# chip-z8530-rs422_split_a.net
KiCad netlist of a schematic drawn in EAGLE
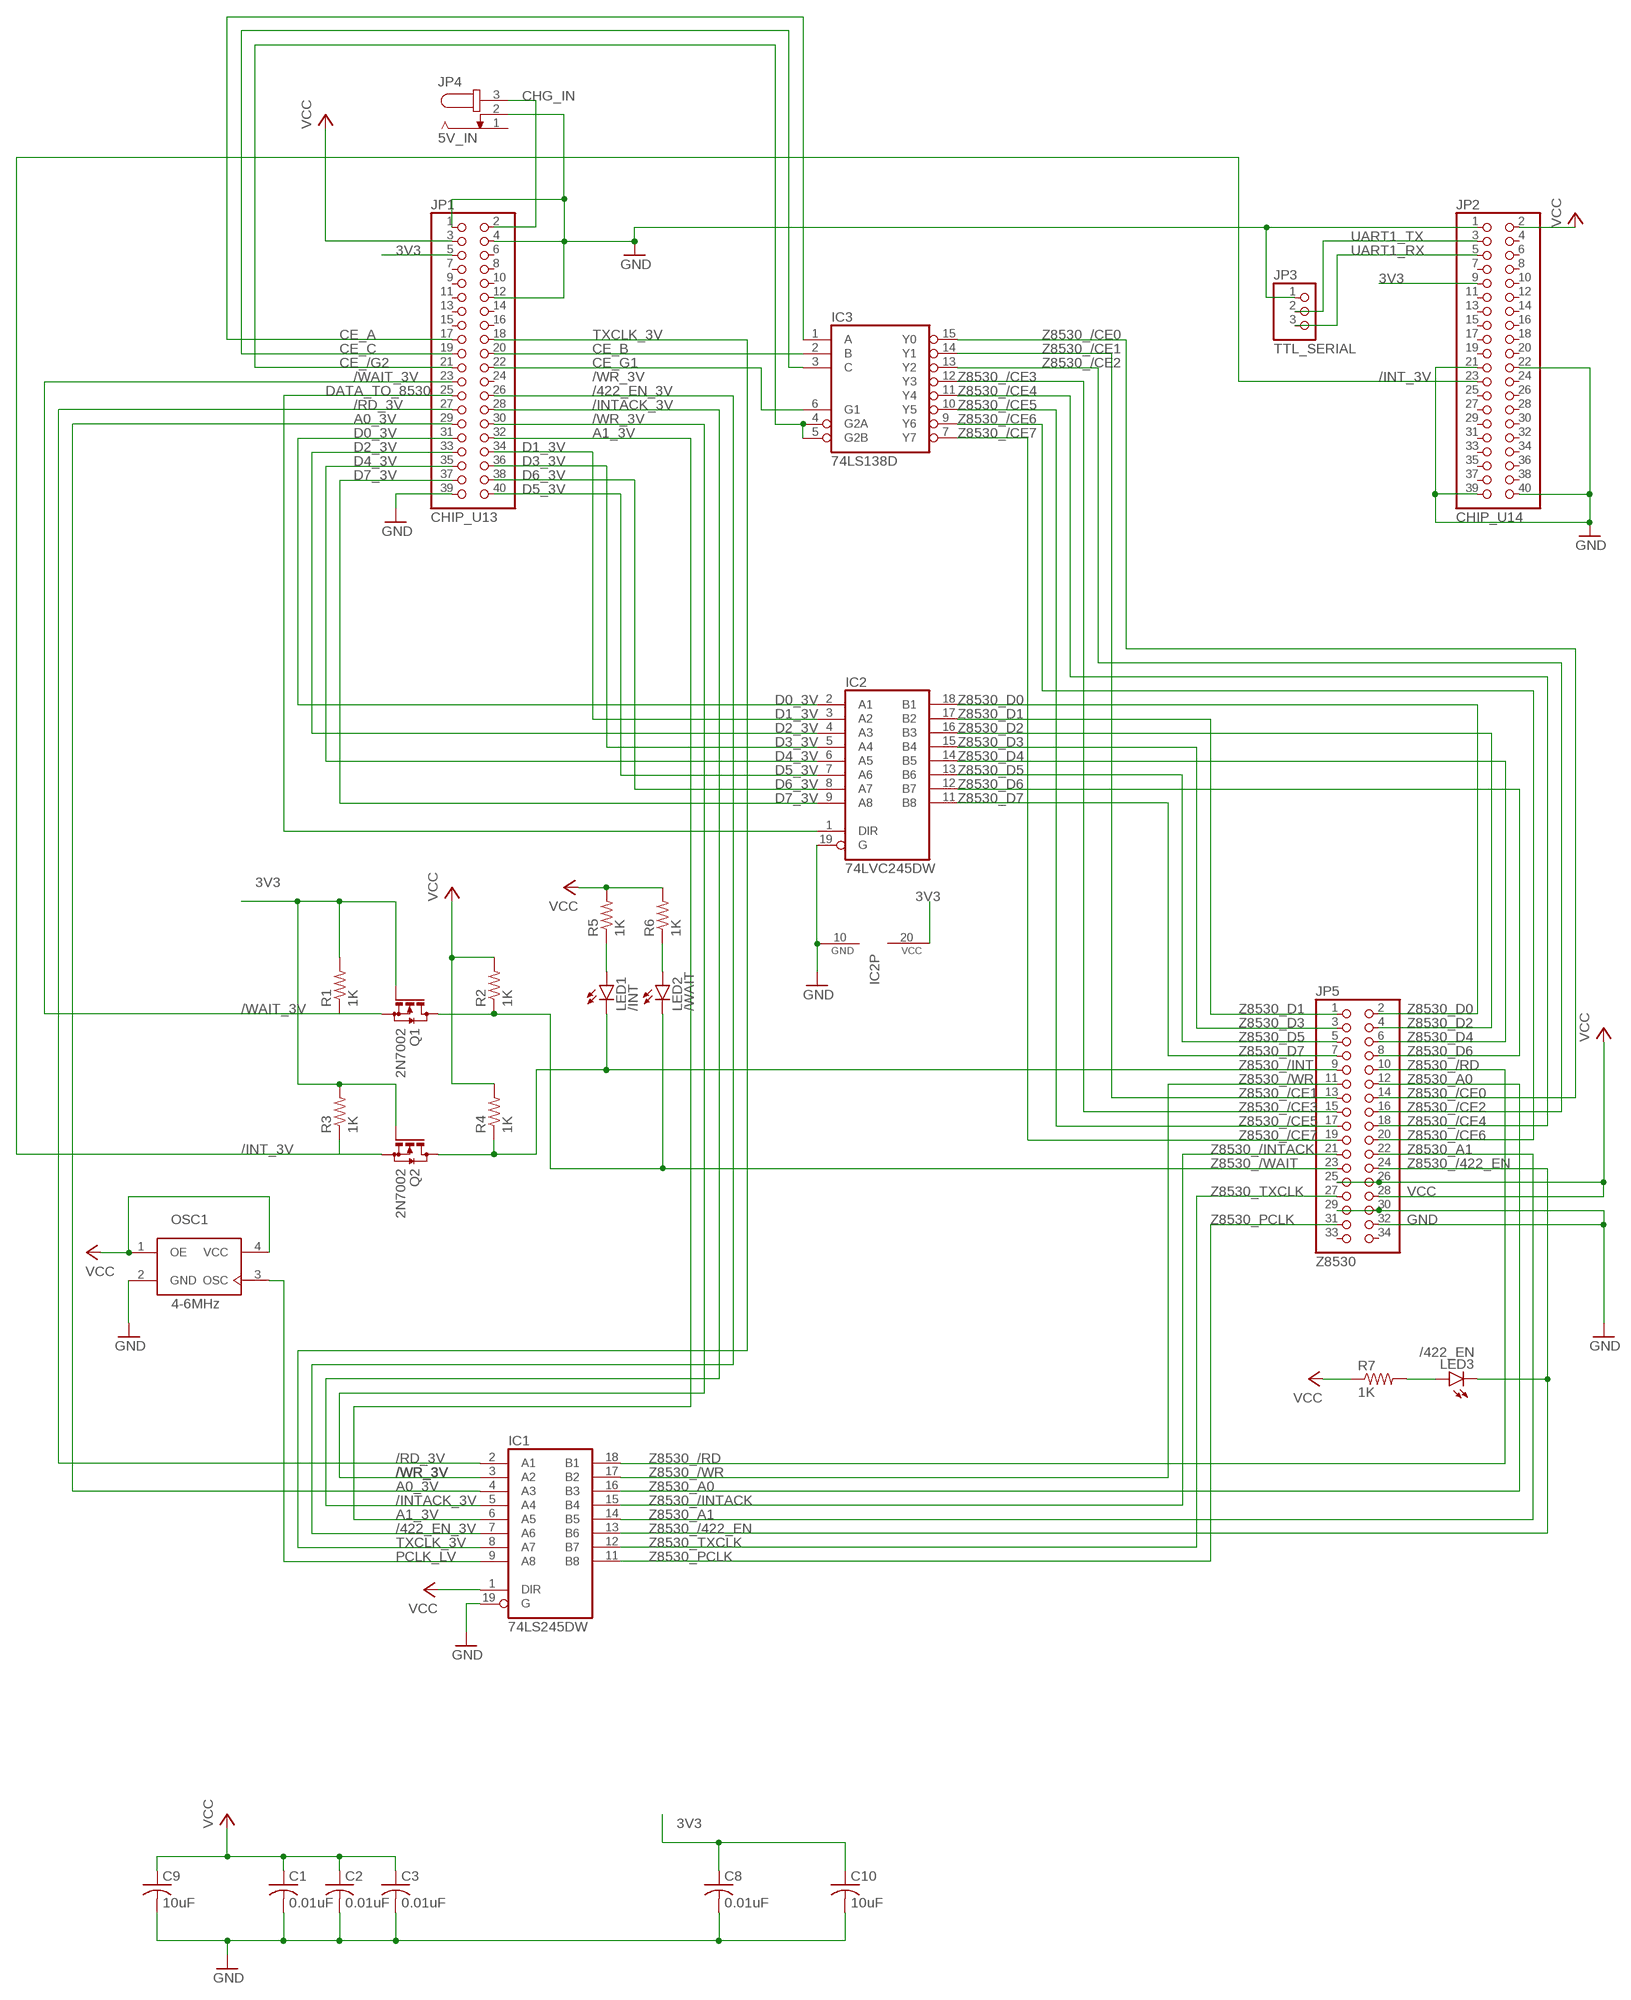
[diagram p0: schematic, sheet 1]

(export (version "E")
  (design (tool "Eeschema 10.0.6"))
  (components
    (comp (ref "C1")
      (value "0.01uF")
      (footprint "eagle-import:C0805")
      (libsource (lib "eagle-import") (part "C-USC0805"))
    )
    (comp (ref "C2")
      (value "0.01uF")
      (footprint "eagle-import:C0805")
      (libsource (lib "eagle-import") (part "C-USC0805"))
    )
    (comp (ref "C3")
      (value "0.01uF")
      (footprint "eagle-import:C0805")
      (libsource (lib "eagle-import") (part "C-USC0805"))
    )
    (comp (ref "C8")
      (value "0.01uF")
      (footprint "eagle-import:C0805")
      (libsource (lib "eagle-import") (part "C-USC0805"))
    )
    (comp (ref "C9")
      (value "10uF")
      (footprint "eagle-import:C0805")
      (libsource (lib "eagle-import") (part "C-USC0805"))
    )
    (comp (ref "C10")
      (value "10uF")
      (footprint "eagle-import:C0805")
      (libsource (lib "eagle-import") (part "C-USC0805"))
    )
    (comp (ref "IC1")
      (value "74LS245DW")
      (footprint "eagle-import:SO20W")
      (libsource (lib "eagle-import") (part "74245DWLS"))
    )
    (comp (ref "IC2")
      (value "74LVC245DW")
      (footprint "eagle-import:SO20W")
      (libsource (lib "eagle-import") (part "74245DWLS"))
    )
    (comp (ref "IC3")
      (value "74LS138D")
      (footprint "eagle-import:SO16")
      (libsource (lib "eagle-import") (part "74138DLS"))
    )
    (comp (ref "JP1")
      (value "CHIP_U13")
      (footprint "eagle-import:2X20")
      (libsource (lib "eagle-import") (part "PINHD-2X20"))
    )
    (comp (ref "JP2")
      (value "CHIP_U14")
      (footprint "eagle-import:2X20")
      (libsource (lib "eagle-import") (part "PINHD-2X20"))
    )
    (comp (ref "JP3")
      (value "TTL_SERIAL")
      (footprint "eagle-import:1X03_90")
      (libsource (lib "eagle-import") (part "PINHD-1X3/90"))
    )
    (comp (ref "JP4")
      (value "5V_IN")
      (footprint "eagle-import:SPC4078")
      (libsource (lib "eagle-import") (part "JACK-PLUG1"))
    )
    (comp (ref "JP5")
      (value "Z8530")
      (footprint "eagle-import:2X17")
      (libsource (lib "eagle-import") (part "PINHD-2X17"))
    )
    (comp (ref "LED1")
      (value "/INT")
      (footprint "eagle-import:LED3MM")
      (libsource (lib "eagle-import") (part "LED3MM"))
    )
    (comp (ref "LED2")
      (value "/WAIT")
      (footprint "eagle-import:LED3MM")
      (libsource (lib "eagle-import") (part "LED3MM"))
    )
    (comp (ref "LED3")
      (value "/422_EN")
      (footprint "eagle-import:LED3MM")
      (libsource (lib "eagle-import") (part "LED3MM"))
    )
    (comp (ref "OSC1")
      (value "4-6MHz")
      (footprint "eagle-import:SG5032")
      (libsource (lib "eagle-import") (part "XO-SMD"))
    )
    (comp (ref "Q1")
      (value "2N7002")
      (footprint "eagle-import:SOT23")
      (libsource (lib "eagle-import") (part "BSS123"))
    )
    (comp (ref "Q2")
      (value "2N7002")
      (footprint "eagle-import:SOT23")
      (libsource (lib "eagle-import") (part "BSS123"))
    )
    (comp (ref "R1")
      (value "1K")
      (footprint "eagle-import:R0805")
      (libsource (lib "eagle-import") (part "R-US_R0805"))
    )
    (comp (ref "R2")
      (value "1K")
      (footprint "eagle-import:R0805")
      (libsource (lib "eagle-import") (part "R-US_R0805"))
    )
    (comp (ref "R3")
      (value "1K")
      (footprint "eagle-import:R0805")
      (libsource (lib "eagle-import") (part "R-US_R0805"))
    )
    (comp (ref "R4")
      (value "1K")
      (footprint "eagle-import:R0805")
      (libsource (lib "eagle-import") (part "R-US_R0805"))
    )
    (comp (ref "R5")
      (value "1K")
      (footprint "eagle-import:R0805")
      (libsource (lib "eagle-import") (part "R-US_R0805"))
    )
    (comp (ref "R6")
      (value "1K")
      (footprint "eagle-import:R0805")
      (libsource (lib "eagle-import") (part "R-US_R0805"))
    )
    (comp (ref "R7")
      (value "1K")
      (footprint "eagle-import:R0805")
      (libsource (lib "eagle-import") (part "R-US_R0805"))
    )
  )
  (nets
    (net (code "1") (name "/3V3") (class "Default")
      (node (ref "C10") (pin "1") (pinfunction "1_1") (pintype "passive"))
      (node (ref "C8") (pin "1") (pinfunction "1_1") (pintype "passive"))
      (node (ref "IC2") (pin "20") (pinfunction "VCC_20") (pintype "power_in"))
      (node (ref "JP1") (pin "5") (pinfunction "5_5") (pintype "passive"))
      (node (ref "JP2") (pin "9") (pinfunction "9_9") (pintype "passive"))
      (node (ref "Q1") (pin "1") (pinfunction "G_1") (pintype "passive"))
      (node (ref "Q2") (pin "1") (pinfunction "G_1") (pintype "passive"))
      (node (ref "R1") (pin "2") (pinfunction "2_2") (pintype "passive"))
      (node (ref "R3") (pin "2") (pinfunction "2_2") (pintype "passive"))
    )
    (net (code "2") (name "/A0_3V") (class "Default")
      (node (ref "IC1") (pin "4") (pinfunction "A3_4") (pintype "bidirectional"))
      (node (ref "JP1") (pin "29") (pinfunction "29_29") (pintype "passive"))
    )
    (net (code "3") (name "/A1_3V") (class "Default")
      (node (ref "IC1") (pin "6") (pinfunction "A5_6") (pintype "bidirectional"))
      (node (ref "JP1") (pin "32") (pinfunction "32_32") (pintype "passive"))
    )
    (net (code "4") (name "/CE_A") (class "Default")
      (node (ref "IC3") (pin "1") (pinfunction "A_1") (pintype "input"))
      (node (ref "JP1") (pin "17") (pinfunction "17_17") (pintype "passive"))
    )
    (net (code "5") (name "/CE_B") (class "Default")
      (node (ref "IC3") (pin "2") (pinfunction "B_2") (pintype "input"))
      (node (ref "JP1") (pin "20") (pinfunction "20_20") (pintype "passive"))
    )
    (net (code "6") (name "/CE_C") (class "Default")
      (node (ref "IC3") (pin "3") (pinfunction "C_3") (pintype "input"))
      (node (ref "JP1") (pin "19") (pinfunction "19_19") (pintype "passive"))
    )
    (net (code "7") (name "/CE_G1") (class "Default")
      (node (ref "IC3") (pin "6") (pinfunction "G1_6") (pintype "input"))
      (node (ref "JP1") (pin "22") (pinfunction "22_22") (pintype "passive"))
    )
    (net (code "8") (name "/CE_{slash}G2") (class "Default")
      (node (ref "IC3") (pin "4") (pinfunction "G2A_4") (pintype "input"))
      (node (ref "IC3") (pin "5") (pinfunction "G2B_5") (pintype "input"))
      (node (ref "JP1") (pin "21") (pinfunction "21_21") (pintype "passive"))
    )
    (net (code "9") (name "/CHG_IN") (class "Default")
      (node (ref "JP1") (pin "2") (pinfunction "2_2") (pintype "passive"))
      (node (ref "JP4") (pin "3") (pinfunction "3_3") (pintype "passive"))
    )
    (net (code "10") (name "/D0_3V") (class "Default")
      (node (ref "IC2") (pin "2") (pinfunction "A1_2") (pintype "bidirectional"))
      (node (ref "JP1") (pin "31") (pinfunction "31_31") (pintype "passive"))
    )
    (net (code "11") (name "/D1_3V") (class "Default")
      (node (ref "IC2") (pin "3") (pinfunction "A2_3") (pintype "bidirectional"))
      (node (ref "JP1") (pin "34") (pinfunction "34_34") (pintype "passive"))
    )
    (net (code "12") (name "/D2_3V") (class "Default")
      (node (ref "IC2") (pin "4") (pinfunction "A3_4") (pintype "bidirectional"))
      (node (ref "JP1") (pin "33") (pinfunction "33_33") (pintype "passive"))
    )
    (net (code "13") (name "/D3_3V") (class "Default")
      (node (ref "IC2") (pin "5") (pinfunction "A4_5") (pintype "bidirectional"))
      (node (ref "JP1") (pin "36") (pinfunction "36_36") (pintype "passive"))
    )
    (net (code "14") (name "/D4_3V") (class "Default")
      (node (ref "IC2") (pin "6") (pinfunction "A5_6") (pintype "bidirectional"))
      (node (ref "JP1") (pin "35") (pinfunction "35_35") (pintype "passive"))
    )
    (net (code "15") (name "/D5_3V") (class "Default")
      (node (ref "IC2") (pin "7") (pinfunction "A6_7") (pintype "bidirectional"))
      (node (ref "JP1") (pin "40") (pinfunction "40_40") (pintype "passive"))
    )
    (net (code "16") (name "/D6_3V") (class "Default")
      (node (ref "IC2") (pin "8") (pinfunction "A7_8") (pintype "bidirectional"))
      (node (ref "JP1") (pin "38") (pinfunction "38_38") (pintype "passive"))
    )
    (net (code "17") (name "/D7_3V") (class "Default")
      (node (ref "IC2") (pin "9") (pinfunction "A8_9") (pintype "bidirectional"))
      (node (ref "JP1") (pin "37") (pinfunction "37_37") (pintype "passive"))
    )
    (net (code "18") (name "/DATA_TO_8530") (class "Default")
      (node (ref "IC2") (pin "1") (pinfunction "DIR_1") (pintype "input"))
      (node (ref "JP1") (pin "25") (pinfunction "25_25") (pintype "passive"))
    )
    (net (code "19") (name "/PCLK_LV") (class "Default")
      (node (ref "IC1") (pin "9") (pinfunction "A8_9") (pintype "bidirectional"))
      (node (ref "OSC1") (pin "3") (pinfunction "OSC_3") (pintype "output"))
    )
    (net (code "20") (name "/TXCLK_3V") (class "Default")
      (node (ref "IC1") (pin "8") (pinfunction "A7_8") (pintype "bidirectional"))
      (node (ref "JP1") (pin "18") (pinfunction "18_18") (pintype "passive"))
    )
    (net (code "21") (name "/UART1_RX") (class "Default")
      (node (ref "JP2") (pin "5") (pinfunction "5_5") (pintype "passive"))
      (node (ref "JP3") (pin "3") (pinfunction "3_3") (pintype "passive"))
    )
    (net (code "22") (name "/UART1_TX") (class "Default")
      (node (ref "JP2") (pin "3") (pinfunction "3_3") (pintype "passive"))
      (node (ref "JP3") (pin "2") (pinfunction "2_2") (pintype "passive"))
    )
    (net (code "23") (name "/Z8530_A0") (class "Default")
      (node (ref "IC1") (pin "16") (pinfunction "B3_16") (pintype "bidirectional"))
      (node (ref "JP5") (pin "12") (pinfunction "12_12") (pintype "passive"))
    )
    (net (code "24") (name "/Z8530_A1") (class "Default")
      (node (ref "IC1") (pin "14") (pinfunction "B5_14") (pintype "bidirectional"))
      (node (ref "JP5") (pin "22") (pinfunction "22_22") (pintype "passive"))
    )
    (net (code "25") (name "/Z8530_D0") (class "Default")
      (node (ref "IC2") (pin "18") (pinfunction "B1_18") (pintype "bidirectional"))
      (node (ref "JP5") (pin "2") (pinfunction "2_2") (pintype "passive"))
    )
    (net (code "26") (name "/Z8530_D1") (class "Default")
      (node (ref "IC2") (pin "17") (pinfunction "B2_17") (pintype "bidirectional"))
      (node (ref "JP5") (pin "1") (pinfunction "1_1") (pintype "passive"))
    )
    (net (code "27") (name "/Z8530_D2") (class "Default")
      (node (ref "IC2") (pin "16") (pinfunction "B3_16") (pintype "bidirectional"))
      (node (ref "JP5") (pin "4") (pinfunction "4_4") (pintype "passive"))
    )
    (net (code "28") (name "/Z8530_D3") (class "Default")
      (node (ref "IC2") (pin "15") (pinfunction "B4_15") (pintype "bidirectional"))
      (node (ref "JP5") (pin "3") (pinfunction "3_3") (pintype "passive"))
    )
    (net (code "29") (name "/Z8530_D4") (class "Default")
      (node (ref "IC2") (pin "14") (pinfunction "B5_14") (pintype "bidirectional"))
      (node (ref "JP5") (pin "6") (pinfunction "6_6") (pintype "passive"))
    )
    (net (code "30") (name "/Z8530_D5") (class "Default")
      (node (ref "IC2") (pin "13") (pinfunction "B6_13") (pintype "bidirectional"))
      (node (ref "JP5") (pin "5") (pinfunction "5_5") (pintype "passive"))
    )
    (net (code "31") (name "/Z8530_D6") (class "Default")
      (node (ref "IC2") (pin "12") (pinfunction "B7_12") (pintype "bidirectional"))
      (node (ref "JP5") (pin "8") (pinfunction "8_8") (pintype "passive"))
    )
    (net (code "32") (name "/Z8530_D7") (class "Default")
      (node (ref "IC2") (pin "11") (pinfunction "B8_11") (pintype "bidirectional"))
      (node (ref "JP5") (pin "7") (pinfunction "7_7") (pintype "passive"))
    )
    (net (code "33") (name "/Z8530_PCLK") (class "Default")
      (node (ref "IC1") (pin "11") (pinfunction "B8_11") (pintype "bidirectional"))
      (node (ref "JP5") (pin "31") (pinfunction "31_31") (pintype "passive"))
    )
    (net (code "34") (name "/Z8530_TXCLK") (class "Default")
      (node (ref "IC1") (pin "12") (pinfunction "B7_12") (pintype "bidirectional"))
      (node (ref "JP5") (pin "27") (pinfunction "27_27") (pintype "passive"))
    )
    (net (code "35") (name "/Z8530_{slash}422_EN") (class "Default")
      (node (ref "IC1") (pin "13") (pinfunction "B6_13") (pintype "bidirectional"))
      (node (ref "JP5") (pin "24") (pinfunction "24_24") (pintype "passive"))
      (node (ref "LED3") (pin "K") (pinfunction "C_K") (pintype "passive"))
    )
    (net (code "36") (name "/Z8530_{slash}CE0") (class "Default")
      (node (ref "IC3") (pin "15") (pinfunction "Y0_15") (pintype "output"))
      (node (ref "JP5") (pin "14") (pinfunction "14_14") (pintype "passive"))
    )
    (net (code "37") (name "/Z8530_{slash}CE1") (class "Default")
      (node (ref "IC3") (pin "14") (pinfunction "Y1_14") (pintype "output"))
      (node (ref "JP5") (pin "13") (pinfunction "13_13") (pintype "passive"))
    )
    (net (code "38") (name "/Z8530_{slash}CE2") (class "Default")
      (node (ref "IC3") (pin "13") (pinfunction "Y2_13") (pintype "output"))
      (node (ref "JP5") (pin "16") (pinfunction "16_16") (pintype "passive"))
    )
    (net (code "39") (name "/Z8530_{slash}CE3") (class "Default")
      (node (ref "IC3") (pin "12") (pinfunction "Y3_12") (pintype "output"))
      (node (ref "JP5") (pin "15") (pinfunction "15_15") (pintype "passive"))
    )
    (net (code "40") (name "/Z8530_{slash}CE4") (class "Default")
      (node (ref "IC3") (pin "11") (pinfunction "Y4_11") (pintype "output"))
      (node (ref "JP5") (pin "18") (pinfunction "18_18") (pintype "passive"))
    )
    (net (code "41") (name "/Z8530_{slash}CE5") (class "Default")
      (node (ref "IC3") (pin "10") (pinfunction "Y5_10") (pintype "output"))
      (node (ref "JP5") (pin "17") (pinfunction "17_17") (pintype "passive"))
    )
    (net (code "42") (name "/Z8530_{slash}CE6") (class "Default")
      (node (ref "IC3") (pin "9") (pinfunction "Y6_9") (pintype "output"))
      (node (ref "JP5") (pin "20") (pinfunction "20_20") (pintype "passive"))
    )
    (net (code "43") (name "/Z8530_{slash}CE7") (class "Default")
      (node (ref "IC3") (pin "7") (pinfunction "Y7_7") (pintype "output"))
      (node (ref "JP5") (pin "19") (pinfunction "19_19") (pintype "passive"))
    )
    (net (code "44") (name "/Z8530_{slash}INT") (class "Default")
      (node (ref "JP5") (pin "9") (pinfunction "9_9") (pintype "passive"))
      (node (ref "LED1") (pin "K") (pinfunction "C_K") (pintype "passive"))
      (node (ref "Q2") (pin "3") (pinfunction "D_3") (pintype "passive"))
      (node (ref "R4") (pin "1") (pinfunction "1_1") (pintype "passive"))
    )
    (net (code "45") (name "/Z8530_{slash}INTACK") (class "Default")
      (node (ref "IC1") (pin "15") (pinfunction "B4_15") (pintype "bidirectional"))
      (node (ref "JP5") (pin "21") (pinfunction "21_21") (pintype "passive"))
    )
    (net (code "46") (name "/Z8530_{slash}RD") (class "Default")
      (node (ref "IC1") (pin "18") (pinfunction "B1_18") (pintype "bidirectional"))
      (node (ref "JP5") (pin "10") (pinfunction "10_10") (pintype "passive"))
    )
    (net (code "47") (name "/Z8530_{slash}WAIT") (class "Default")
      (node (ref "JP5") (pin "23") (pinfunction "23_23") (pintype "passive"))
      (node (ref "LED2") (pin "K") (pinfunction "C_K") (pintype "passive"))
      (node (ref "Q1") (pin "3") (pinfunction "D_3") (pintype "passive"))
      (node (ref "R2") (pin "1") (pinfunction "1_1") (pintype "passive"))
    )
    (net (code "48") (name "/Z8530_{slash}WR") (class "Default")
      (node (ref "IC1") (pin "17") (pinfunction "B2_17") (pintype "bidirectional"))
      (node (ref "JP5") (pin "11") (pinfunction "11_11") (pintype "passive"))
    )
    (net (code "49") (name "/{slash}422_EN_3V") (class "Default")
      (node (ref "IC1") (pin "7") (pinfunction "A6_7") (pintype "bidirectional"))
      (node (ref "JP1") (pin "26") (pinfunction "26_26") (pintype "passive"))
    )
    (net (code "50") (name "/{slash}INTACK_3V") (class "Default")
      (node (ref "IC1") (pin "5") (pinfunction "A4_5") (pintype "bidirectional"))
      (node (ref "JP1") (pin "28") (pinfunction "28_28") (pintype "passive"))
    )
    (net (code "51") (name "/{slash}INT_3V") (class "Default")
      (node (ref "JP2") (pin "23") (pinfunction "23_23") (pintype "passive"))
      (node (ref "Q2") (pin "2") (pinfunction "S_2") (pintype "passive"))
      (node (ref "R3") (pin "1") (pinfunction "1_1") (pintype "passive"))
    )
    (net (code "52") (name "/{slash}RD_3V") (class "Default")
      (node (ref "IC1") (pin "2") (pinfunction "A1_2") (pintype "bidirectional"))
      (node (ref "JP1") (pin "27") (pinfunction "27_27") (pintype "passive"))
    )
    (net (code "53") (name "/{slash}WAIT_3V") (class "Default")
      (node (ref "JP1") (pin "23") (pinfunction "23_23") (pintype "passive"))
      (node (ref "Q1") (pin "2") (pinfunction "S_2") (pintype "passive"))
      (node (ref "R1") (pin "1") (pinfunction "1_1") (pintype "passive"))
    )
    (net (code "54") (name "/{slash}WR_3V") (class "Default")
      (node (ref "IC1") (pin "3") (pinfunction "A2_3") (pintype "bidirectional"))
      (node (ref "JP1") (pin "30") (pinfunction "30_30") (pintype "passive"))
    )
    (net (code "55") (name "GND") (class "Default")
      (node (ref "C1") (pin "2") (pinfunction "2_2") (pintype "passive"))
      (node (ref "C10") (pin "2") (pinfunction "2_2") (pintype "passive"))
      (node (ref "C2") (pin "2") (pinfunction "2_2") (pintype "passive"))
      (node (ref "C3") (pin "2") (pinfunction "2_2") (pintype "passive"))
      (node (ref "C8") (pin "2") (pinfunction "2_2") (pintype "passive"))
      (node (ref "C9") (pin "2") (pinfunction "2_2") (pintype "passive"))
      (node (ref "IC1") (pin "19") (pinfunction "G_19") (pintype "input"))
      (node (ref "IC2") (pin "10") (pinfunction "GND_10") (pintype "power_in"))
      (node (ref "IC2") (pin "19") (pinfunction "G_19") (pintype "input"))
      (node (ref "JP1") (pin "1") (pinfunction "1_1") (pintype "passive"))
      (node (ref "JP1") (pin "12") (pinfunction "12_12") (pintype "passive"))
      (node (ref "JP1") (pin "39") (pinfunction "39_39") (pintype "passive"))
      (node (ref "JP1") (pin "4") (pinfunction "4_4") (pintype "passive"))
      (node (ref "JP2") (pin "1") (pinfunction "1_1") (pintype "passive"))
      (node (ref "JP2") (pin "21") (pinfunction "21_21") (pintype "passive"))
      (node (ref "JP2") (pin "22") (pinfunction "22_22") (pintype "passive"))
      (node (ref "JP2") (pin "39") (pinfunction "39_39") (pintype "passive"))
      (node (ref "JP2") (pin "40") (pinfunction "40_40") (pintype "passive"))
      (node (ref "JP3") (pin "1") (pinfunction "1_1") (pintype "passive"))
      (node (ref "JP4") (pin "2") (pinfunction "2_2") (pintype "passive"))
      (node (ref "JP5") (pin "29") (pinfunction "29_29") (pintype "passive"))
      (node (ref "JP5") (pin "30") (pinfunction "30_30") (pintype "passive"))
      (node (ref "JP5") (pin "32") (pinfunction "32_32") (pintype "passive"))
      (node (ref "OSC1") (pin "2") (pinfunction "GND_2") (pintype "power_in"))
    )
    (net (code "56") (name "Net-(LED1-PadA)") (class "Default")
      (node (ref "LED1") (pin "A") (pinfunction "A_A") (pintype "passive"))
      (node (ref "R5") (pin "1") (pinfunction "1_1") (pintype "passive"))
    )
    (net (code "57") (name "Net-(LED2-PadA)") (class "Default")
      (node (ref "LED2") (pin "A") (pinfunction "A_A") (pintype "passive"))
      (node (ref "R6") (pin "1") (pinfunction "1_1") (pintype "passive"))
    )
    (net (code "58") (name "Net-(LED3-PadA)") (class "Default")
      (node (ref "LED3") (pin "A") (pinfunction "A_A") (pintype "passive"))
      (node (ref "R7") (pin "2") (pinfunction "2_2") (pintype "passive"))
    )
    (net (code "59") (name "VCC") (class "Default")
      (node (ref "C1") (pin "1") (pinfunction "1_1") (pintype "passive"))
      (node (ref "C2") (pin "1") (pinfunction "1_1") (pintype "passive"))
      (node (ref "C3") (pin "1") (pinfunction "1_1") (pintype "passive"))
      (node (ref "C9") (pin "1") (pinfunction "1_1") (pintype "passive"))
      (node (ref "IC1") (pin "1") (pinfunction "DIR_1") (pintype "input"))
      (node (ref "JP1") (pin "3") (pinfunction "3_3") (pintype "passive"))
      (node (ref "JP2") (pin "2") (pinfunction "2_2") (pintype "passive"))
      (node (ref "JP5") (pin "25") (pinfunction "25_25") (pintype "passive"))
      (node (ref "JP5") (pin "26") (pinfunction "26_26") (pintype "passive"))
      (node (ref "JP5") (pin "28") (pinfunction "28_28") (pintype "passive"))
      (node (ref "OSC1") (pin "1") (pinfunction "OE_1") (pintype "input"))
      (node (ref "OSC1") (pin "4") (pinfunction "VCC_4") (pintype "power_in"))
      (node (ref "R2") (pin "2") (pinfunction "2_2") (pintype "passive"))
      (node (ref "R4") (pin "2") (pinfunction "2_2") (pintype "passive"))
      (node (ref "R5") (pin "2") (pinfunction "2_2") (pintype "passive"))
      (node (ref "R6") (pin "2") (pinfunction "2_2") (pintype "passive"))
      (node (ref "R7") (pin "1") (pinfunction "1_1") (pintype "passive"))
    )
    (net (code "60") (name "unconnected-(JP1-Pad6)") (class "Default")
      (node (ref "JP1") (pin "6") (pinfunction "6_6") (pintype "passive"))
    )
    (net (code "61") (name "unconnected-(JP1-Pad7)") (class "Default")
      (node (ref "JP1") (pin "7") (pinfunction "7_7") (pintype "passive"))
    )
    (net (code "62") (name "unconnected-(JP1-Pad8)") (class "Default")
      (node (ref "JP1") (pin "8") (pinfunction "8_8") (pintype "passive"))
    )
    (net (code "63") (name "unconnected-(JP1-Pad9)") (class "Default")
      (node (ref "JP1") (pin "9") (pinfunction "9_9") (pintype "passive"))
    )
    (net (code "64") (name "unconnected-(JP1-Pad10)") (class "Default")
      (node (ref "JP1") (pin "10") (pinfunction "10_10") (pintype "passive"))
    )
    (net (code "65") (name "unconnected-(JP1-Pad11)") (class "Default")
      (node (ref "JP1") (pin "11") (pinfunction "11_11") (pintype "passive"))
    )
    (net (code "66") (name "unconnected-(JP1-Pad13)") (class "Default")
      (node (ref "JP1") (pin "13") (pinfunction "13_13") (pintype "passive"))
    )
    (net (code "67") (name "unconnected-(JP1-Pad14)") (class "Default")
      (node (ref "JP1") (pin "14") (pinfunction "14_14") (pintype "passive"))
    )
    (net (code "68") (name "unconnected-(JP1-Pad15)") (class "Default")
      (node (ref "JP1") (pin "15") (pinfunction "15_15") (pintype "passive"))
    )
    (net (code "69") (name "unconnected-(JP1-Pad16)") (class "Default")
      (node (ref "JP1") (pin "16") (pinfunction "16_16") (pintype "passive"))
    )
    (net (code "70") (name "unconnected-(JP1-Pad24)") (class "Default")
      (node (ref "JP1") (pin "24") (pinfunction "24_24") (pintype "passive"))
    )
    (net (code "71") (name "unconnected-(JP2-Pad4)") (class "Default")
      (node (ref "JP2") (pin "4") (pinfunction "4_4") (pintype "passive"))
    )
    (net (code "72") (name "unconnected-(JP2-Pad6)") (class "Default")
      (node (ref "JP2") (pin "6") (pinfunction "6_6") (pintype "passive"))
    )
    (net (code "73") (name "unconnected-(JP2-Pad7)") (class "Default")
      (node (ref "JP2") (pin "7") (pinfunction "7_7") (pintype "passive"))
    )
    (net (code "74") (name "unconnected-(JP2-Pad8)") (class "Default")
      (node (ref "JP2") (pin "8") (pinfunction "8_8") (pintype "passive"))
    )
    (net (code "75") (name "unconnected-(JP2-Pad10)") (class "Default")
      (node (ref "JP2") (pin "10") (pinfunction "10_10") (pintype "passive"))
    )
    (net (code "76") (name "unconnected-(JP2-Pad11)") (class "Default")
      (node (ref "JP2") (pin "11") (pinfunction "11_11") (pintype "passive"))
    )
    (net (code "77") (name "unconnected-(JP2-Pad12)") (class "Default")
      (node (ref "JP2") (pin "12") (pinfunction "12_12") (pintype "passive"))
    )
    (net (code "78") (name "unconnected-(JP2-Pad13)") (class "Default")
      (node (ref "JP2") (pin "13") (pinfunction "13_13") (pintype "passive"))
    )
    (net (code "79") (name "unconnected-(JP2-Pad14)") (class "Default")
      (node (ref "JP2") (pin "14") (pinfunction "14_14") (pintype "passive"))
    )
    (net (code "80") (name "unconnected-(JP2-Pad15)") (class "Default")
      (node (ref "JP2") (pin "15") (pinfunction "15_15") (pintype "passive"))
    )
    (net (code "81") (name "unconnected-(JP2-Pad16)") (class "Default")
      (node (ref "JP2") (pin "16") (pinfunction "16_16") (pintype "passive"))
    )
    (net (code "82") (name "unconnected-(JP2-Pad17)") (class "Default")
      (node (ref "JP2") (pin "17") (pinfunction "17_17") (pintype "passive"))
    )
    (net (code "83") (name "unconnected-(JP2-Pad18)") (class "Default")
      (node (ref "JP2") (pin "18") (pinfunction "18_18") (pintype "passive"))
    )
    (net (code "84") (name "unconnected-(JP2-Pad19)") (class "Default")
      (node (ref "JP2") (pin "19") (pinfunction "19_19") (pintype "passive"))
    )
    (net (code "85") (name "unconnected-(JP2-Pad20)") (class "Default")
      (node (ref "JP2") (pin "20") (pinfunction "20_20") (pintype "passive"))
    )
    (net (code "86") (name "unconnected-(JP2-Pad24)") (class "Default")
      (node (ref "JP2") (pin "24") (pinfunction "24_24") (pintype "passive"))
    )
    (net (code "87") (name "unconnected-(JP2-Pad25)") (class "Default")
      (node (ref "JP2") (pin "25") (pinfunction "25_25") (pintype "passive"))
    )
    (net (code "88") (name "unconnected-(JP2-Pad26)") (class "Default")
      (node (ref "JP2") (pin "26") (pinfunction "26_26") (pintype "passive"))
    )
    (net (code "89") (name "unconnected-(JP2-Pad27)") (class "Default")
      (node (ref "JP2") (pin "27") (pinfunction "27_27") (pintype "passive"))
    )
    (net (code "90") (name "unconnected-(JP2-Pad28)") (class "Default")
      (node (ref "JP2") (pin "28") (pinfunction "28_28") (pintype "passive"))
    )
    (net (code "91") (name "unconnected-(JP2-Pad29)") (class "Default")
      (node (ref "JP2") (pin "29") (pinfunction "29_29") (pintype "passive"))
    )
    (net (code "92") (name "unconnected-(JP2-Pad30)") (class "Default")
      (node (ref "JP2") (pin "30") (pinfunction "30_30") (pintype "passive"))
    )
    (net (code "93") (name "unconnected-(JP2-Pad31)") (class "Default")
      (node (ref "JP2") (pin "31") (pinfunction "31_31") (pintype "passive"))
    )
    (net (code "94") (name "unconnected-(JP2-Pad32)") (class "Default")
      (node (ref "JP2") (pin "32") (pinfunction "32_32") (pintype "passive"))
    )
    (net (code "95") (name "unconnected-(JP2-Pad33)") (class "Default")
      (node (ref "JP2") (pin "33") (pinfunction "33_33") (pintype "passive"))
    )
    (net (code "96") (name "unconnected-(JP2-Pad34)") (class "Default")
      (node (ref "JP2") (pin "34") (pinfunction "34_34") (pintype "passive"))
    )
    (net (code "97") (name "unconnected-(JP2-Pad35)") (class "Default")
      (node (ref "JP2") (pin "35") (pinfunction "35_35") (pintype "passive"))
    )
    (net (code "98") (name "unconnected-(JP2-Pad36)") (class "Default")
      (node (ref "JP2") (pin "36") (pinfunction "36_36") (pintype "passive"))
    )
    (net (code "99") (name "unconnected-(JP2-Pad37)") (class "Default")
      (node (ref "JP2") (pin "37") (pinfunction "37_37") (pintype "passive"))
    )
    (net (code "100") (name "unconnected-(JP2-Pad38)") (class "Default")
      (node (ref "JP2") (pin "38") (pinfunction "38_38") (pintype "passive"))
    )
    (net (code "101") (name "unconnected-(JP4-Pad1)") (class "Default")
      (node (ref "JP4") (pin "1") (pinfunction "1_1") (pintype "passive"))
    )
    (net (code "102") (name "unconnected-(JP5-Pad33)") (class "Default")
      (node (ref "JP5") (pin "33") (pinfunction "33_33") (pintype "passive"))
    )
    (net (code "103") (name "unconnected-(JP5-Pad34)") (class "Default")
      (node (ref "JP5") (pin "34") (pinfunction "34_34") (pintype "passive"))
    )
  )
)
